# ProProject_Standalone_Non_Auto_Modules_2.net
KiCad netlist of a schematic drawn in EasyEDA Pro
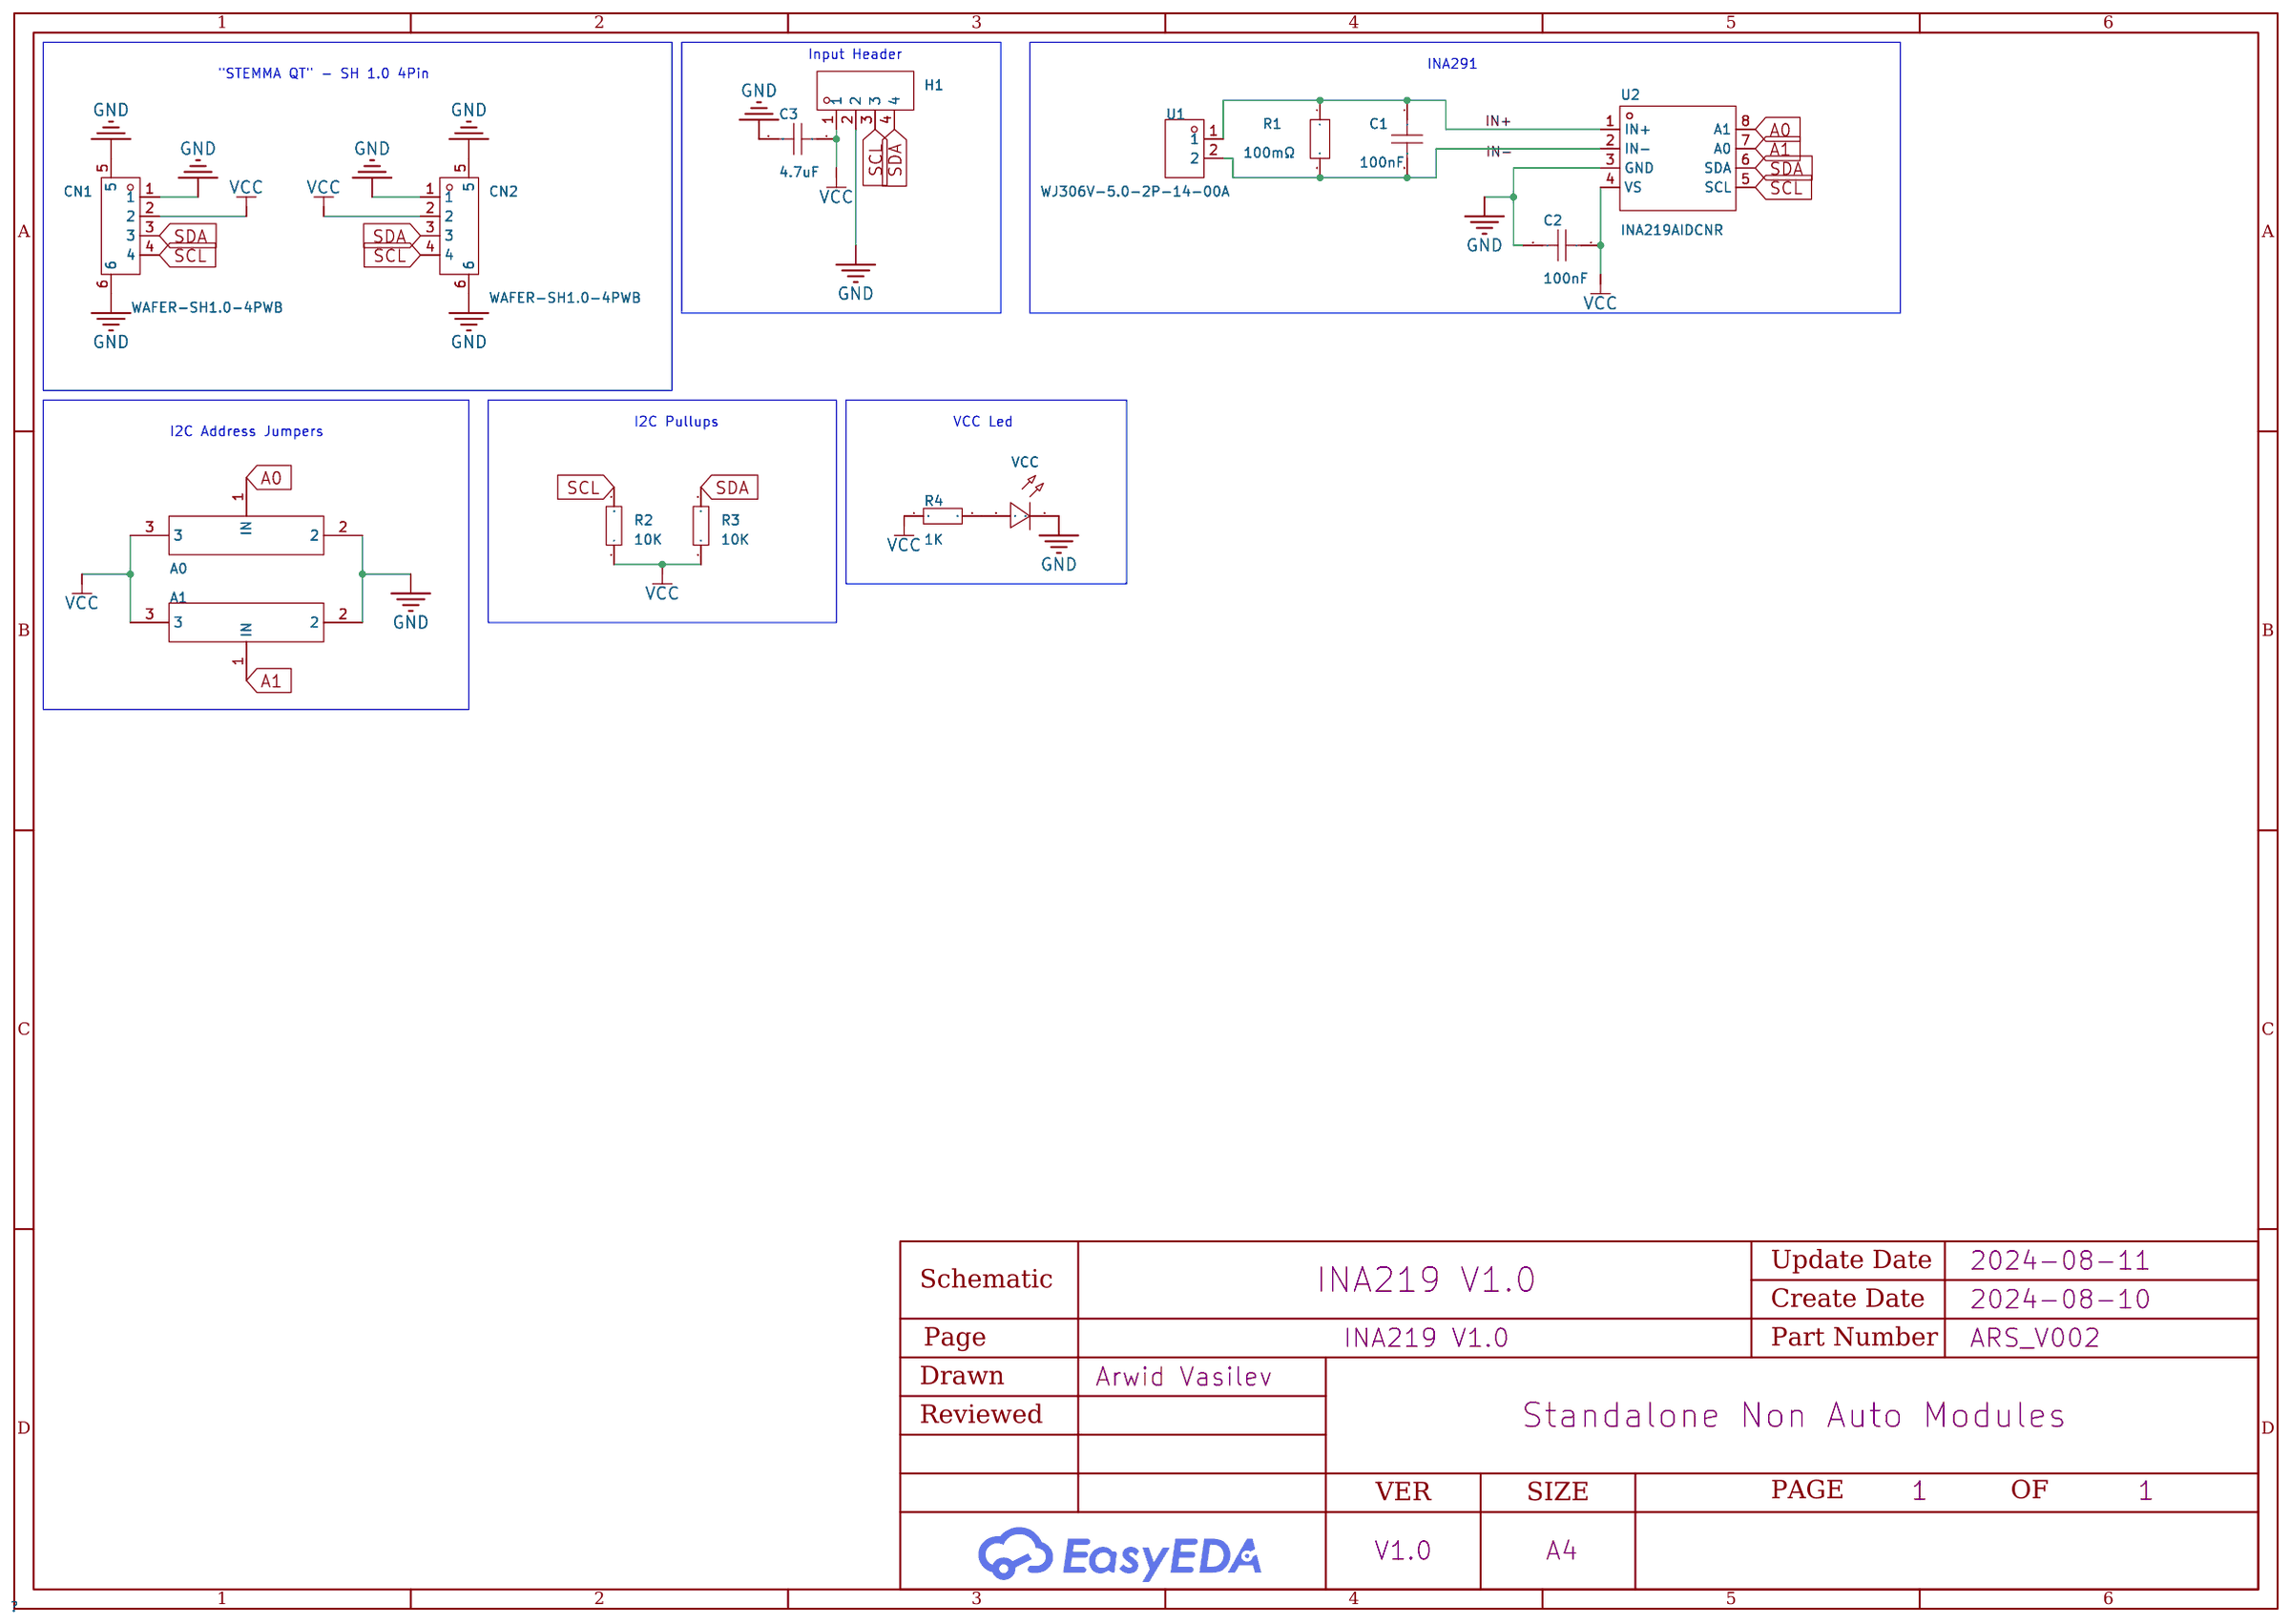
[diagram p0: schematic sheet]

(export (version "E")
  (design (tool "Eeschema 10.0.6"))
  (components
    (comp (ref "A0")
      (value "~")
      (footprint "easyedapro:3 way solder Jumper")
      (libsource (lib "easyedapro") (part "3 Way Solder Jumper"))
    )
    (comp (ref "A1")
      (value "~")
      (footprint "easyedapro:3 way solder Jumper")
      (libsource (lib "easyedapro") (part "3 Way Solder Jumper"))
    )
    (comp (ref "C1")
      (value "100nF")
      (footprint "easyedapro:C0603")
      (libsource (lib "easyedapro") (part "CAP"))
    )
    (comp (ref "C2")
      (value "100nF")
      (footprint "easyedapro:C0603")
      (libsource (lib "easyedapro") (part "CAP"))
    )
    (comp (ref "C3")
      (value "4.7uF")
      (footprint "easyedapro:C0603")
      (libsource (lib "easyedapro") (part "CAP"))
    )
    (comp (ref "CN1")
      (value "WAFER-SH1.0-4PWB")
      (footprint "easyedapro:CONN-SMD_4P-P1.00_WAFER-SH1.0-4PWB")
      (fields (field (name "Manufacturer") "XUNPU(讯普)"))
      (libsource (lib "easyedapro") (part "WAFER-SH1.0-4PWB"))
    )
    (comp (ref "CN2")
      (value "WAFER-SH1.0-4PWB")
      (footprint "easyedapro:CONN-SMD_4P-P1.00_WAFER-SH1.0-4PWB")
      (fields (field (name "Manufacturer") "XUNPU(讯普)"))
      (libsource (lib "easyedapro") (part "WAFER-SH1.0-4PWB"))
    )
    (comp (ref "H1")
      (value "~")
      (footprint "easyedapro:HDR-TH_4P-P2.54-V-M")
      (libsource (lib "easyedapro") (part "PZ254V-11-04P"))
    )
    (comp (ref "R1")
      (value "100mΩ")
      (footprint "easyedapro:RES-SMD_L6.4-W3.2-R2512")
      (fields
        (field (name "Manufacturer Part") "HoJLR2512-3W-100mR-1%")
        (field (name "Manufacturer") "Milliohm(毫欧)")
      )
      (libsource (lib "easyedapro") (part "HOJLR2512-3W-100MR-1%"))
    )
    (comp (ref "R2") (value "10K") (footprint "easyedapro:R0201") (libsource (lib "easyedapro") (part "Res")))
    (comp (ref "R3") (value "10K") (footprint "easyedapro:R0201") (libsource (lib "easyedapro") (part "Res")))
    (comp (ref "R4") (value "1K") (footprint "easyedapro:R0201") (libsource (lib "easyedapro") (part "Res")))
    (comp (ref "U1")
      (value "WJ306V-5.0-2P-14-00A")
      (footprint "easyedapro:CONN-TH_2P-P5.00_L7.6-W10.0")
      (fields (field (name "Manufacturer") "KANGNEX(康奈克斯电气)"))
      (libsource (lib "easyedapro") (part "WJ306V-5.0-2P-14-00A"))
    )
    (comp (ref "U2")
      (value "INA219AIDCNR")
      (footprint "easyedapro:SOT-23-8_L3.0-W1.7-P0.65-LS2.8-BR")
      (fields (field (name "Manufacturer") "TI(德州仪器)"))
      (libsource (lib "easyedapro") (part "INA219AIDCNR"))
    )
    (comp (ref "VCC")
      (value "~")
      (footprint "easyedapro:LED0603-RD_GREEN")
      (libsource (lib "easyedapro") (part "LED_G"))
    )
  )
  (nets
    (net (code "1") (name "/IN+") (class "Default")
      (node (ref "C1") (pin "1") (pinfunction "1_1") (pintype "input"))
      (node (ref "R1") (pin "1") (pinfunction "1_1") (pintype "unspecified"))
      (node (ref "U1") (pin "1") (pinfunction "1_1") (pintype "unspecified"))
      (node (ref "U2") (pin "1") (pinfunction "IN+_1") (pintype "unspecified"))
    )
    (net (code "2") (name "/IN-") (class "Default")
      (node (ref "C1") (pin "2") (pinfunction "2_2") (pintype "input"))
      (node (ref "R1") (pin "2") (pinfunction "2_2") (pintype "unspecified"))
      (node (ref "U1") (pin "2") (pinfunction "2_2") (pintype "unspecified"))
      (node (ref "U2") (pin "2") (pinfunction "IN-_2") (pintype "unspecified"))
    )
    (net (code "3") (name "A0") (class "Default")
      (node (ref "A0") (pin "1") (pinfunction "IN_1") (pintype "input"))
      (node (ref "U2") (pin "8") (pinfunction "A1_8") (pintype "unspecified"))
    )
    (net (code "4") (name "A1") (class "Default")
      (node (ref "A1") (pin "1") (pinfunction "IN_1") (pintype "input"))
      (node (ref "U2") (pin "7") (pinfunction "A0_7") (pintype "unspecified"))
    )
    (net (code "5") (name "GND") (class "Default")
      (node (ref "A0") (pin "2") (pinfunction "2_2") (pintype "input"))
      (node (ref "A1") (pin "2") (pinfunction "2_2") (pintype "input"))
      (node (ref "C2") (pin "2") (pinfunction "2_2") (pintype "input"))
      (node (ref "C3") (pin "2") (pinfunction "2_2") (pintype "input"))
      (node (ref "CN1") (pin "1") (pinfunction "1_1") (pintype "unspecified"))
      (node (ref "CN1") (pin "5") (pinfunction "5_5") (pintype "unspecified"))
      (node (ref "CN1") (pin "6") (pinfunction "6_6") (pintype "unspecified"))
      (node (ref "CN2") (pin "1") (pinfunction "1_1") (pintype "unspecified"))
      (node (ref "CN2") (pin "5") (pinfunction "5_5") (pintype "unspecified"))
      (node (ref "CN2") (pin "6") (pinfunction "6_6") (pintype "unspecified"))
      (node (ref "H1") (pin "2") (pinfunction "2_2") (pintype "unspecified"))
      (node (ref "U2") (pin "3") (pinfunction "GND_3") (pintype "unspecified"))
      (node (ref "VCC") (pin "1") (pinfunction "C_1") (pintype "input"))
    )
    (net (code "6") (name "Net-(VCC-A)") (class "Default")
      (node (ref "R4") (pin "2") (pinfunction "2_2") (pintype "input"))
      (node (ref "VCC") (pin "2") (pinfunction "A_2") (pintype "input"))
    )
    (net (code "7") (name "SCL") (class "Default")
      (node (ref "CN1") (pin "4") (pinfunction "4_4") (pintype "unspecified"))
      (node (ref "CN2") (pin "4") (pinfunction "4_4") (pintype "unspecified"))
      (node (ref "H1") (pin "3") (pinfunction "3_3") (pintype "unspecified"))
      (node (ref "R2") (pin "2") (pinfunction "2_2") (pintype "input"))
      (node (ref "U2") (pin "5") (pinfunction "SCL_5") (pintype "unspecified"))
    )
    (net (code "8") (name "SDA") (class "Default")
      (node (ref "CN1") (pin "3") (pinfunction "3_3") (pintype "unspecified"))
      (node (ref "CN2") (pin "3") (pinfunction "3_3") (pintype "unspecified"))
      (node (ref "H1") (pin "4") (pinfunction "4_4") (pintype "unspecified"))
      (node (ref "R3") (pin "2") (pinfunction "2_2") (pintype "input"))
      (node (ref "U2") (pin "6") (pinfunction "SDA_6") (pintype "unspecified"))
    )
    (net (code "9") (name "VCC") (class "Default")
      (node (ref "A0") (pin "3") (pinfunction "3_3") (pintype "input"))
      (node (ref "A1") (pin "3") (pinfunction "3_3") (pintype "input"))
      (node (ref "C2") (pin "1") (pinfunction "1_1") (pintype "input"))
      (node (ref "C3") (pin "1") (pinfunction "1_1") (pintype "input"))
      (node (ref "CN1") (pin "2") (pinfunction "2_2") (pintype "unspecified"))
      (node (ref "CN2") (pin "2") (pinfunction "2_2") (pintype "unspecified"))
      (node (ref "H1") (pin "1") (pinfunction "1_1") (pintype "unspecified"))
      (node (ref "R2") (pin "1") (pinfunction "1_1") (pintype "input"))
      (node (ref "R3") (pin "1") (pinfunction "1_1") (pintype "input"))
      (node (ref "R4") (pin "1") (pinfunction "1_1") (pintype "input"))
      (node (ref "U2") (pin "4") (pinfunction "VS_4") (pintype "unspecified"))
    )
  )
)
